# Decoup_Cap_1.net
KiCad netlist of a schematic drawn in Altium Designer
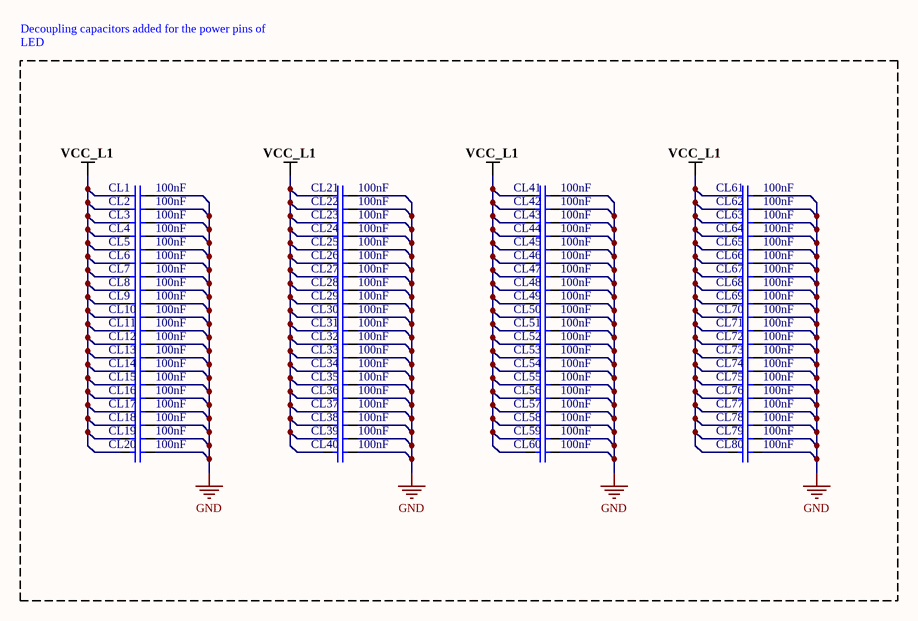
[diagram p0: Decoup_Cap 1.SchDoc]

(export (version "E")
  (design (tool "Eeschema 10.0.6"))
  (components
    (comp (ref "CL1")
      (value "100nF")
      (footprint "Cap0402")
      (description "Cap Ceramic 0.1uF 25V X7R 10% SMD 0402 125C Paper T/R")
      (fields
        (field (name "MANUFACTURER") "Yageo")
        (field (name "MANUFACTURER PART NUMBER") "CC0402KRX7R8BB104")
      )
      (libsource (lib "TT_IntLib") (part "CC0402KRX7R8BB104"))
    )
    (comp (ref "CL2")
      (value "100nF")
      (footprint "Cap0402")
      (description "Cap Ceramic 0.1uF 25V X7R 10% SMD 0402 125C Paper T/R")
      (fields
        (field (name "MANUFACTURER") "Yageo")
        (field (name "MANUFACTURER PART NUMBER") "CC0402KRX7R8BB104")
      )
      (libsource (lib "TT_IntLib") (part "CC0402KRX7R8BB104"))
    )
    (comp (ref "CL3")
      (value "100nF")
      (footprint "Cap0402")
      (description "Cap Ceramic 0.1uF 25V X7R 10% SMD 0402 125C Paper T/R")
      (fields
        (field (name "MANUFACTURER") "Yageo")
        (field (name "MANUFACTURER PART NUMBER") "CC0402KRX7R8BB104")
      )
      (libsource (lib "TT_IntLib") (part "CC0402KRX7R8BB104"))
    )
    (comp (ref "CL4")
      (value "100nF")
      (footprint "Cap0402")
      (description "Cap Ceramic 0.1uF 25V X7R 10% SMD 0402 125C Paper T/R")
      (fields
        (field (name "MANUFACTURER") "Yageo")
        (field (name "MANUFACTURER PART NUMBER") "CC0402KRX7R8BB104")
      )
      (libsource (lib "TT_IntLib") (part "CC0402KRX7R8BB104"))
    )
    (comp (ref "CL5")
      (value "100nF")
      (footprint "Cap0402")
      (description "Cap Ceramic 0.1uF 25V X7R 10% SMD 0402 125C Paper T/R")
      (fields
        (field (name "MANUFACTURER") "Yageo")
        (field (name "MANUFACTURER PART NUMBER") "CC0402KRX7R8BB104")
      )
      (libsource (lib "TT_IntLib") (part "CC0402KRX7R8BB104"))
    )
    (comp (ref "CL6")
      (value "100nF")
      (footprint "Cap0402")
      (description "Cap Ceramic 0.1uF 25V X7R 10% SMD 0402 125C Paper T/R")
      (fields
        (field (name "MANUFACTURER") "Yageo")
        (field (name "MANUFACTURER PART NUMBER") "CC0402KRX7R8BB104")
      )
      (libsource (lib "TT_IntLib") (part "CC0402KRX7R8BB104"))
    )
    (comp (ref "CL7")
      (value "100nF")
      (footprint "Cap0402")
      (description "Cap Ceramic 0.1uF 25V X7R 10% SMD 0402 125C Paper T/R")
      (fields
        (field (name "MANUFACTURER") "Yageo")
        (field (name "MANUFACTURER PART NUMBER") "CC0402KRX7R8BB104")
      )
      (libsource (lib "TT_IntLib") (part "CC0402KRX7R8BB104"))
    )
    (comp (ref "CL8")
      (value "100nF")
      (footprint "Cap0402")
      (description "Cap Ceramic 0.1uF 25V X7R 10% SMD 0402 125C Paper T/R")
      (fields
        (field (name "MANUFACTURER") "Yageo")
        (field (name "MANUFACTURER PART NUMBER") "CC0402KRX7R8BB104")
      )
      (libsource (lib "TT_IntLib") (part "CC0402KRX7R8BB104"))
    )
    (comp (ref "CL9")
      (value "100nF")
      (footprint "Cap0402")
      (description "Cap Ceramic 0.1uF 25V X7R 10% SMD 0402 125C Paper T/R")
      (fields
        (field (name "MANUFACTURER") "Yageo")
        (field (name "MANUFACTURER PART NUMBER") "CC0402KRX7R8BB104")
      )
      (libsource (lib "TT_IntLib") (part "CC0402KRX7R8BB104"))
    )
    (comp (ref "CL10")
      (value "100nF")
      (footprint "Cap0402")
      (description "Cap Ceramic 0.1uF 25V X7R 10% SMD 0402 125C Paper T/R")
      (fields
        (field (name "MANUFACTURER") "Yageo")
        (field (name "MANUFACTURER PART NUMBER") "CC0402KRX7R8BB104")
      )
      (libsource (lib "TT_IntLib") (part "CC0402KRX7R8BB104"))
    )
    (comp (ref "CL11")
      (value "100nF")
      (footprint "Cap0402")
      (description "Cap Ceramic 0.1uF 25V X7R 10% SMD 0402 125C Paper T/R")
      (fields
        (field (name "MANUFACTURER") "Yageo")
        (field (name "MANUFACTURER PART NUMBER") "CC0402KRX7R8BB104")
      )
      (libsource (lib "TT_IntLib") (part "CC0402KRX7R8BB104"))
    )
    (comp (ref "CL12")
      (value "100nF")
      (footprint "Cap0402")
      (description "Cap Ceramic 0.1uF 25V X7R 10% SMD 0402 125C Paper T/R")
      (fields
        (field (name "MANUFACTURER") "Yageo")
        (field (name "MANUFACTURER PART NUMBER") "CC0402KRX7R8BB104")
      )
      (libsource (lib "TT_IntLib") (part "CC0402KRX7R8BB104"))
    )
    (comp (ref "CL13")
      (value "100nF")
      (footprint "Cap0402")
      (description "Cap Ceramic 0.1uF 25V X7R 10% SMD 0402 125C Paper T/R")
      (fields
        (field (name "MANUFACTURER") "Yageo")
        (field (name "MANUFACTURER PART NUMBER") "CC0402KRX7R8BB104")
      )
      (libsource (lib "TT_IntLib") (part "CC0402KRX7R8BB104"))
    )
    (comp (ref "CL14")
      (value "100nF")
      (footprint "Cap0402")
      (description "Cap Ceramic 0.1uF 25V X7R 10% SMD 0402 125C Paper T/R")
      (fields
        (field (name "MANUFACTURER") "Yageo")
        (field (name "MANUFACTURER PART NUMBER") "CC0402KRX7R8BB104")
      )
      (libsource (lib "TT_IntLib") (part "CC0402KRX7R8BB104"))
    )
    (comp (ref "CL15")
      (value "100nF")
      (footprint "Cap0402")
      (description "Cap Ceramic 0.1uF 25V X7R 10% SMD 0402 125C Paper T/R")
      (fields
        (field (name "MANUFACTURER") "Yageo")
        (field (name "MANUFACTURER PART NUMBER") "CC0402KRX7R8BB104")
      )
      (libsource (lib "TT_IntLib") (part "CC0402KRX7R8BB104"))
    )
    (comp (ref "CL16")
      (value "100nF")
      (footprint "Cap0402")
      (description "Cap Ceramic 0.1uF 25V X7R 10% SMD 0402 125C Paper T/R")
      (fields
        (field (name "MANUFACTURER") "Yageo")
        (field (name "MANUFACTURER PART NUMBER") "CC0402KRX7R8BB104")
      )
      (libsource (lib "TT_IntLib") (part "CC0402KRX7R8BB104"))
    )
    (comp (ref "CL17")
      (value "100nF")
      (footprint "Cap0402")
      (description "Cap Ceramic 0.1uF 25V X7R 10% SMD 0402 125C Paper T/R")
      (fields
        (field (name "MANUFACTURER") "Yageo")
        (field (name "MANUFACTURER PART NUMBER") "CC0402KRX7R8BB104")
      )
      (libsource (lib "TT_IntLib") (part "CC0402KRX7R8BB104"))
    )
    (comp (ref "CL18")
      (value "100nF")
      (footprint "Cap0402")
      (description "Cap Ceramic 0.1uF 25V X7R 10% SMD 0402 125C Paper T/R")
      (fields
        (field (name "MANUFACTURER") "Yageo")
        (field (name "MANUFACTURER PART NUMBER") "CC0402KRX7R8BB104")
      )
      (libsource (lib "TT_IntLib") (part "CC0402KRX7R8BB104"))
    )
    (comp (ref "CL19")
      (value "100nF")
      (footprint "Cap0402")
      (description "Cap Ceramic 0.1uF 25V X7R 10% SMD 0402 125C Paper T/R")
      (fields
        (field (name "MANUFACTURER") "Yageo")
        (field (name "MANUFACTURER PART NUMBER") "CC0402KRX7R8BB104")
      )
      (libsource (lib "TT_IntLib") (part "CC0402KRX7R8BB104"))
    )
    (comp (ref "CL20")
      (value "100nF")
      (footprint "Cap0402")
      (description "Cap Ceramic 0.1uF 25V X7R 10% SMD 0402 125C Paper T/R")
      (fields
        (field (name "MANUFACTURER") "Yageo")
        (field (name "MANUFACTURER PART NUMBER") "CC0402KRX7R8BB104")
      )
      (libsource (lib "TT_IntLib") (part "CC0402KRX7R8BB104"))
    )
    (comp (ref "CL21")
      (value "100nF")
      (footprint "Cap0402")
      (description "Cap Ceramic 0.1uF 25V X7R 10% SMD 0402 125C Paper T/R")
      (fields
        (field (name "MANUFACTURER") "Yageo")
        (field (name "MANUFACTURER PART NUMBER") "CC0402KRX7R8BB104")
      )
      (libsource (lib "TT_IntLib") (part "CC0402KRX7R8BB104"))
    )
    (comp (ref "CL22")
      (value "100nF")
      (footprint "Cap0402")
      (description "Cap Ceramic 0.1uF 25V X7R 10% SMD 0402 125C Paper T/R")
      (fields
        (field (name "MANUFACTURER") "Yageo")
        (field (name "MANUFACTURER PART NUMBER") "CC0402KRX7R8BB104")
      )
      (libsource (lib "TT_IntLib") (part "CC0402KRX7R8BB104"))
    )
    (comp (ref "CL23")
      (value "100nF")
      (footprint "Cap0402")
      (description "Cap Ceramic 0.1uF 25V X7R 10% SMD 0402 125C Paper T/R")
      (fields
        (field (name "MANUFACTURER") "Yageo")
        (field (name "MANUFACTURER PART NUMBER") "CC0402KRX7R8BB104")
      )
      (libsource (lib "TT_IntLib") (part "CC0402KRX7R8BB104"))
    )
    (comp (ref "CL24")
      (value "100nF")
      (footprint "Cap0402")
      (description "Cap Ceramic 0.1uF 25V X7R 10% SMD 0402 125C Paper T/R")
      (fields
        (field (name "MANUFACTURER") "Yageo")
        (field (name "MANUFACTURER PART NUMBER") "CC0402KRX7R8BB104")
      )
      (libsource (lib "TT_IntLib") (part "CC0402KRX7R8BB104"))
    )
    (comp (ref "CL25")
      (value "100nF")
      (footprint "Cap0402")
      (description "Cap Ceramic 0.1uF 25V X7R 10% SMD 0402 125C Paper T/R")
      (fields
        (field (name "MANUFACTURER") "Yageo")
        (field (name "MANUFACTURER PART NUMBER") "CC0402KRX7R8BB104")
      )
      (libsource (lib "TT_IntLib") (part "CC0402KRX7R8BB104"))
    )
    (comp (ref "CL26")
      (value "100nF")
      (footprint "Cap0402")
      (description "Cap Ceramic 0.1uF 25V X7R 10% SMD 0402 125C Paper T/R")
      (fields
        (field (name "MANUFACTURER") "Yageo")
        (field (name "MANUFACTURER PART NUMBER") "CC0402KRX7R8BB104")
      )
      (libsource (lib "TT_IntLib") (part "CC0402KRX7R8BB104"))
    )
    (comp (ref "CL27")
      (value "100nF")
      (footprint "Cap0402")
      (description "Cap Ceramic 0.1uF 25V X7R 10% SMD 0402 125C Paper T/R")
      (fields
        (field (name "MANUFACTURER") "Yageo")
        (field (name "MANUFACTURER PART NUMBER") "CC0402KRX7R8BB104")
      )
      (libsource (lib "TT_IntLib") (part "CC0402KRX7R8BB104"))
    )
    (comp (ref "CL28")
      (value "100nF")
      (footprint "Cap0402")
      (description "Cap Ceramic 0.1uF 25V X7R 10% SMD 0402 125C Paper T/R")
      (fields
        (field (name "MANUFACTURER") "Yageo")
        (field (name "MANUFACTURER PART NUMBER") "CC0402KRX7R8BB104")
      )
      (libsource (lib "TT_IntLib") (part "CC0402KRX7R8BB104"))
    )
    (comp (ref "CL29")
      (value "100nF")
      (footprint "Cap0402")
      (description "Cap Ceramic 0.1uF 25V X7R 10% SMD 0402 125C Paper T/R")
      (fields
        (field (name "MANUFACTURER") "Yageo")
        (field (name "MANUFACTURER PART NUMBER") "CC0402KRX7R8BB104")
      )
      (libsource (lib "TT_IntLib") (part "CC0402KRX7R8BB104"))
    )
    (comp (ref "CL30")
      (value "100nF")
      (footprint "Cap0402")
      (description "Cap Ceramic 0.1uF 25V X7R 10% SMD 0402 125C Paper T/R")
      (fields
        (field (name "MANUFACTURER") "Yageo")
        (field (name "MANUFACTURER PART NUMBER") "CC0402KRX7R8BB104")
      )
      (libsource (lib "TT_IntLib") (part "CC0402KRX7R8BB104"))
    )
    (comp (ref "CL31")
      (value "100nF")
      (footprint "Cap0402")
      (description "Cap Ceramic 0.1uF 25V X7R 10% SMD 0402 125C Paper T/R")
      (fields
        (field (name "MANUFACTURER") "Yageo")
        (field (name "MANUFACTURER PART NUMBER") "CC0402KRX7R8BB104")
      )
      (libsource (lib "TT_IntLib") (part "CC0402KRX7R8BB104"))
    )
    (comp (ref "CL32")
      (value "100nF")
      (footprint "Cap0402")
      (description "Cap Ceramic 0.1uF 25V X7R 10% SMD 0402 125C Paper T/R")
      (fields
        (field (name "MANUFACTURER") "Yageo")
        (field (name "MANUFACTURER PART NUMBER") "CC0402KRX7R8BB104")
      )
      (libsource (lib "TT_IntLib") (part "CC0402KRX7R8BB104"))
    )
    (comp (ref "CL33")
      (value "100nF")
      (footprint "Cap0402")
      (description "Cap Ceramic 0.1uF 25V X7R 10% SMD 0402 125C Paper T/R")
      (fields
        (field (name "MANUFACTURER") "Yageo")
        (field (name "MANUFACTURER PART NUMBER") "CC0402KRX7R8BB104")
      )
      (libsource (lib "TT_IntLib") (part "CC0402KRX7R8BB104"))
    )
    (comp (ref "CL34")
      (value "100nF")
      (footprint "Cap0402")
      (description "Cap Ceramic 0.1uF 25V X7R 10% SMD 0402 125C Paper T/R")
      (fields
        (field (name "MANUFACTURER") "Yageo")
        (field (name "MANUFACTURER PART NUMBER") "CC0402KRX7R8BB104")
      )
      (libsource (lib "TT_IntLib") (part "CC0402KRX7R8BB104"))
    )
    (comp (ref "CL35")
      (value "100nF")
      (footprint "Cap0402")
      (description "Cap Ceramic 0.1uF 25V X7R 10% SMD 0402 125C Paper T/R")
      (fields
        (field (name "MANUFACTURER") "Yageo")
        (field (name "MANUFACTURER PART NUMBER") "CC0402KRX7R8BB104")
      )
      (libsource (lib "TT_IntLib") (part "CC0402KRX7R8BB104"))
    )
    (comp (ref "CL36")
      (value "100nF")
      (footprint "Cap0402")
      (description "Cap Ceramic 0.1uF 25V X7R 10% SMD 0402 125C Paper T/R")
      (fields
        (field (name "MANUFACTURER") "Yageo")
        (field (name "MANUFACTURER PART NUMBER") "CC0402KRX7R8BB104")
      )
      (libsource (lib "TT_IntLib") (part "CC0402KRX7R8BB104"))
    )
    (comp (ref "CL37")
      (value "100nF")
      (footprint "Cap0402")
      (description "Cap Ceramic 0.1uF 25V X7R 10% SMD 0402 125C Paper T/R")
      (fields
        (field (name "MANUFACTURER") "Yageo")
        (field (name "MANUFACTURER PART NUMBER") "CC0402KRX7R8BB104")
      )
      (libsource (lib "TT_IntLib") (part "CC0402KRX7R8BB104"))
    )
    (comp (ref "CL38")
      (value "100nF")
      (footprint "Cap0402")
      (description "Cap Ceramic 0.1uF 25V X7R 10% SMD 0402 125C Paper T/R")
      (fields
        (field (name "MANUFACTURER") "Yageo")
        (field (name "MANUFACTURER PART NUMBER") "CC0402KRX7R8BB104")
      )
      (libsource (lib "TT_IntLib") (part "CC0402KRX7R8BB104"))
    )
    (comp (ref "CL39")
      (value "100nF")
      (footprint "Cap0402")
      (description "Cap Ceramic 0.1uF 25V X7R 10% SMD 0402 125C Paper T/R")
      (fields
        (field (name "MANUFACTURER") "Yageo")
        (field (name "MANUFACTURER PART NUMBER") "CC0402KRX7R8BB104")
      )
      (libsource (lib "TT_IntLib") (part "CC0402KRX7R8BB104"))
    )
    (comp (ref "CL40")
      (value "100nF")
      (footprint "Cap0402")
      (description "Cap Ceramic 0.1uF 25V X7R 10% SMD 0402 125C Paper T/R")
      (fields
        (field (name "MANUFACTURER") "Yageo")
        (field (name "MANUFACTURER PART NUMBER") "CC0402KRX7R8BB104")
      )
      (libsource (lib "TT_IntLib") (part "CC0402KRX7R8BB104"))
    )
    (comp (ref "CL41")
      (value "100nF")
      (footprint "Cap0402")
      (description "Cap Ceramic 0.1uF 25V X7R 10% SMD 0402 125C Paper T/R")
      (fields
        (field (name "MANUFACTURER") "Yageo")
        (field (name "MANUFACTURER PART NUMBER") "CC0402KRX7R8BB104")
      )
      (libsource (lib "TT_IntLib") (part "CC0402KRX7R8BB104"))
    )
    (comp (ref "CL42")
      (value "100nF")
      (footprint "Cap0402")
      (description "Cap Ceramic 0.1uF 25V X7R 10% SMD 0402 125C Paper T/R")
      (fields
        (field (name "MANUFACTURER") "Yageo")
        (field (name "MANUFACTURER PART NUMBER") "CC0402KRX7R8BB104")
      )
      (libsource (lib "TT_IntLib") (part "CC0402KRX7R8BB104"))
    )
    (comp (ref "CL43")
      (value "100nF")
      (footprint "Cap0402")
      (description "Cap Ceramic 0.1uF 25V X7R 10% SMD 0402 125C Paper T/R")
      (fields
        (field (name "MANUFACTURER") "Yageo")
        (field (name "MANUFACTURER PART NUMBER") "CC0402KRX7R8BB104")
      )
      (libsource (lib "TT_IntLib") (part "CC0402KRX7R8BB104"))
    )
    (comp (ref "CL44")
      (value "100nF")
      (footprint "Cap0402")
      (description "Cap Ceramic 0.1uF 25V X7R 10% SMD 0402 125C Paper T/R")
      (fields
        (field (name "MANUFACTURER") "Yageo")
        (field (name "MANUFACTURER PART NUMBER") "CC0402KRX7R8BB104")
      )
      (libsource (lib "TT_IntLib") (part "CC0402KRX7R8BB104"))
    )
    (comp (ref "CL45")
      (value "100nF")
      (footprint "Cap0402")
      (description "Cap Ceramic 0.1uF 25V X7R 10% SMD 0402 125C Paper T/R")
      (fields
        (field (name "MANUFACTURER") "Yageo")
        (field (name "MANUFACTURER PART NUMBER") "CC0402KRX7R8BB104")
      )
      (libsource (lib "TT_IntLib") (part "CC0402KRX7R8BB104"))
    )
    (comp (ref "CL46")
      (value "100nF")
      (footprint "Cap0402")
      (description "Cap Ceramic 0.1uF 25V X7R 10% SMD 0402 125C Paper T/R")
      (fields
        (field (name "MANUFACTURER") "Yageo")
        (field (name "MANUFACTURER PART NUMBER") "CC0402KRX7R8BB104")
      )
      (libsource (lib "TT_IntLib") (part "CC0402KRX7R8BB104"))
    )
    (comp (ref "CL47")
      (value "100nF")
      (footprint "Cap0402")
      (description "Cap Ceramic 0.1uF 25V X7R 10% SMD 0402 125C Paper T/R")
      (fields
        (field (name "MANUFACTURER") "Yageo")
        (field (name "MANUFACTURER PART NUMBER") "CC0402KRX7R8BB104")
      )
      (libsource (lib "TT_IntLib") (part "CC0402KRX7R8BB104"))
    )
    (comp (ref "CL48")
      (value "100nF")
      (footprint "Cap0402")
      (description "Cap Ceramic 0.1uF 25V X7R 10% SMD 0402 125C Paper T/R")
      (fields
        (field (name "MANUFACTURER") "Yageo")
        (field (name "MANUFACTURER PART NUMBER") "CC0402KRX7R8BB104")
      )
      (libsource (lib "TT_IntLib") (part "CC0402KRX7R8BB104"))
    )
    (comp (ref "CL49")
      (value "100nF")
      (footprint "Cap0402")
      (description "Cap Ceramic 0.1uF 25V X7R 10% SMD 0402 125C Paper T/R")
      (fields
        (field (name "MANUFACTURER") "Yageo")
        (field (name "MANUFACTURER PART NUMBER") "CC0402KRX7R8BB104")
      )
      (libsource (lib "TT_IntLib") (part "CC0402KRX7R8BB104"))
    )
    (comp (ref "CL50")
      (value "100nF")
      (footprint "Cap0402")
      (description "Cap Ceramic 0.1uF 25V X7R 10% SMD 0402 125C Paper T/R")
      (fields
        (field (name "MANUFACTURER") "Yageo")
        (field (name "MANUFACTURER PART NUMBER") "CC0402KRX7R8BB104")
      )
      (libsource (lib "TT_IntLib") (part "CC0402KRX7R8BB104"))
    )
    (comp (ref "CL51")
      (value "100nF")
      (footprint "Cap0402")
      (description "Cap Ceramic 0.1uF 25V X7R 10% SMD 0402 125C Paper T/R")
      (fields
        (field (name "MANUFACTURER") "Yageo")
        (field (name "MANUFACTURER PART NUMBER") "CC0402KRX7R8BB104")
      )
      (libsource (lib "TT_IntLib") (part "CC0402KRX7R8BB104"))
    )
    (comp (ref "CL52")
      (value "100nF")
      (footprint "Cap0402")
      (description "Cap Ceramic 0.1uF 25V X7R 10% SMD 0402 125C Paper T/R")
      (fields
        (field (name "MANUFACTURER") "Yageo")
        (field (name "MANUFACTURER PART NUMBER") "CC0402KRX7R8BB104")
      )
      (libsource (lib "TT_IntLib") (part "CC0402KRX7R8BB104"))
    )
    (comp (ref "CL53")
      (value "100nF")
      (footprint "Cap0402")
      (description "Cap Ceramic 0.1uF 25V X7R 10% SMD 0402 125C Paper T/R")
      (fields
        (field (name "MANUFACTURER") "Yageo")
        (field (name "MANUFACTURER PART NUMBER") "CC0402KRX7R8BB104")
      )
      (libsource (lib "TT_IntLib") (part "CC0402KRX7R8BB104"))
    )
    (comp (ref "CL54")
      (value "100nF")
      (footprint "Cap0402")
      (description "Cap Ceramic 0.1uF 25V X7R 10% SMD 0402 125C Paper T/R")
      (fields
        (field (name "MANUFACTURER") "Yageo")
        (field (name "MANUFACTURER PART NUMBER") "CC0402KRX7R8BB104")
      )
      (libsource (lib "TT_IntLib") (part "CC0402KRX7R8BB104"))
    )
    (comp (ref "CL55")
      (value "100nF")
      (footprint "Cap0402")
      (description "Cap Ceramic 0.1uF 25V X7R 10% SMD 0402 125C Paper T/R")
      (fields
        (field (name "MANUFACTURER") "Yageo")
        (field (name "MANUFACTURER PART NUMBER") "CC0402KRX7R8BB104")
      )
      (libsource (lib "TT_IntLib") (part "CC0402KRX7R8BB104"))
    )
    (comp (ref "CL56")
      (value "100nF")
      (footprint "Cap0402")
      (description "Cap Ceramic 0.1uF 25V X7R 10% SMD 0402 125C Paper T/R")
      (fields
        (field (name "MANUFACTURER") "Yageo")
        (field (name "MANUFACTURER PART NUMBER") "CC0402KRX7R8BB104")
      )
      (libsource (lib "TT_IntLib") (part "CC0402KRX7R8BB104"))
    )
    (comp (ref "CL57")
      (value "100nF")
      (footprint "Cap0402")
      (description "Cap Ceramic 0.1uF 25V X7R 10% SMD 0402 125C Paper T/R")
      (fields
        (field (name "MANUFACTURER") "Yageo")
        (field (name "MANUFACTURER PART NUMBER") "CC0402KRX7R8BB104")
      )
      (libsource (lib "TT_IntLib") (part "CC0402KRX7R8BB104"))
    )
    (comp (ref "CL58")
      (value "100nF")
      (footprint "Cap0402")
      (description "Cap Ceramic 0.1uF 25V X7R 10% SMD 0402 125C Paper T/R")
      (fields
        (field (name "MANUFACTURER") "Yageo")
        (field (name "MANUFACTURER PART NUMBER") "CC0402KRX7R8BB104")
      )
      (libsource (lib "TT_IntLib") (part "CC0402KRX7R8BB104"))
    )
    (comp (ref "CL59")
      (value "100nF")
      (footprint "Cap0402")
      (description "Cap Ceramic 0.1uF 25V X7R 10% SMD 0402 125C Paper T/R")
      (fields
        (field (name "MANUFACTURER") "Yageo")
        (field (name "MANUFACTURER PART NUMBER") "CC0402KRX7R8BB104")
      )
      (libsource (lib "TT_IntLib") (part "CC0402KRX7R8BB104"))
    )
    (comp (ref "CL60")
      (value "100nF")
      (footprint "Cap0402")
      (description "Cap Ceramic 0.1uF 25V X7R 10% SMD 0402 125C Paper T/R")
      (fields
        (field (name "MANUFACTURER") "Yageo")
        (field (name "MANUFACTURER PART NUMBER") "CC0402KRX7R8BB104")
      )
      (libsource (lib "TT_IntLib") (part "CC0402KRX7R8BB104"))
    )
    (comp (ref "CL61")
      (value "100nF")
      (footprint "Cap0402")
      (description "Cap Ceramic 0.1uF 25V X7R 10% SMD 0402 125C Paper T/R")
      (fields
        (field (name "MANUFACTURER") "Yageo")
        (field (name "MANUFACTURER PART NUMBER") "CC0402KRX7R8BB104")
      )
      (libsource (lib "TT_IntLib") (part "CC0402KRX7R8BB104"))
    )
    (comp (ref "CL62")
      (value "100nF")
      (footprint "Cap0402")
      (description "Cap Ceramic 0.1uF 25V X7R 10% SMD 0402 125C Paper T/R")
      (fields
        (field (name "MANUFACTURER") "Yageo")
        (field (name "MANUFACTURER PART NUMBER") "CC0402KRX7R8BB104")
      )
      (libsource (lib "TT_IntLib") (part "CC0402KRX7R8BB104"))
    )
    (comp (ref "CL63")
      (value "100nF")
      (footprint "Cap0402")
      (description "Cap Ceramic 0.1uF 25V X7R 10% SMD 0402 125C Paper T/R")
      (fields
        (field (name "MANUFACTURER") "Yageo")
        (field (name "MANUFACTURER PART NUMBER") "CC0402KRX7R8BB104")
      )
      (libsource (lib "TT_IntLib") (part "CC0402KRX7R8BB104"))
    )
    (comp (ref "CL64")
      (value "100nF")
      (footprint "Cap0402")
      (description "Cap Ceramic 0.1uF 25V X7R 10% SMD 0402 125C Paper T/R")
      (fields
        (field (name "MANUFACTURER") "Yageo")
        (field (name "MANUFACTURER PART NUMBER") "CC0402KRX7R8BB104")
      )
      (libsource (lib "TT_IntLib") (part "CC0402KRX7R8BB104"))
    )
    (comp (ref "CL65")
      (value "100nF")
      (footprint "Cap0402")
      (description "Cap Ceramic 0.1uF 25V X7R 10% SMD 0402 125C Paper T/R")
      (fields
        (field (name "MANUFACTURER") "Yageo")
        (field (name "MANUFACTURER PART NUMBER") "CC0402KRX7R8BB104")
      )
      (libsource (lib "TT_IntLib") (part "CC0402KRX7R8BB104"))
    )
    (comp (ref "CL66")
      (value "100nF")
      (footprint "Cap0402")
      (description "Cap Ceramic 0.1uF 25V X7R 10% SMD 0402 125C Paper T/R")
      (fields
        (field (name "MANUFACTURER") "Yageo")
        (field (name "MANUFACTURER PART NUMBER") "CC0402KRX7R8BB104")
      )
      (libsource (lib "TT_IntLib") (part "CC0402KRX7R8BB104"))
    )
    (comp (ref "CL67")
      (value "100nF")
      (footprint "Cap0402")
      (description "Cap Ceramic 0.1uF 25V X7R 10% SMD 0402 125C Paper T/R")
      (fields
        (field (name "MANUFACTURER") "Yageo")
        (field (name "MANUFACTURER PART NUMBER") "CC0402KRX7R8BB104")
      )
      (libsource (lib "TT_IntLib") (part "CC0402KRX7R8BB104"))
    )
    (comp (ref "CL68")
      (value "100nF")
      (footprint "Cap0402")
      (description "Cap Ceramic 0.1uF 25V X7R 10% SMD 0402 125C Paper T/R")
      (fields
        (field (name "MANUFACTURER") "Yageo")
        (field (name "MANUFACTURER PART NUMBER") "CC0402KRX7R8BB104")
      )
      (libsource (lib "TT_IntLib") (part "CC0402KRX7R8BB104"))
    )
    (comp (ref "CL69")
      (value "100nF")
      (footprint "Cap0402")
      (description "Cap Ceramic 0.1uF 25V X7R 10% SMD 0402 125C Paper T/R")
      (fields
        (field (name "MANUFACTURER") "Yageo")
        (field (name "MANUFACTURER PART NUMBER") "CC0402KRX7R8BB104")
      )
      (libsource (lib "TT_IntLib") (part "CC0402KRX7R8BB104"))
    )
    (comp (ref "CL70")
      (value "100nF")
      (footprint "Cap0402")
      (description "Cap Ceramic 0.1uF 25V X7R 10% SMD 0402 125C Paper T/R")
      (fields
        (field (name "MANUFACTURER") "Yageo")
        (field (name "MANUFACTURER PART NUMBER") "CC0402KRX7R8BB104")
      )
      (libsource (lib "TT_IntLib") (part "CC0402KRX7R8BB104"))
    )
    (comp (ref "CL71")
      (value "100nF")
      (footprint "Cap0402")
      (description "Cap Ceramic 0.1uF 25V X7R 10% SMD 0402 125C Paper T/R")
      (fields
        (field (name "MANUFACTURER") "Yageo")
        (field (name "MANUFACTURER PART NUMBER") "CC0402KRX7R8BB104")
      )
      (libsource (lib "TT_IntLib") (part "CC0402KRX7R8BB104"))
    )
    (comp (ref "CL72")
      (value "100nF")
      (footprint "Cap0402")
      (description "Cap Ceramic 0.1uF 25V X7R 10% SMD 0402 125C Paper T/R")
      (fields
        (field (name "MANUFACTURER") "Yageo")
        (field (name "MANUFACTURER PART NUMBER") "CC0402KRX7R8BB104")
      )
      (libsource (lib "TT_IntLib") (part "CC0402KRX7R8BB104"))
    )
    (comp (ref "CL73")
      (value "100nF")
      (footprint "Cap0402")
      (description "Cap Ceramic 0.1uF 25V X7R 10% SMD 0402 125C Paper T/R")
      (fields
        (field (name "MANUFACTURER") "Yageo")
        (field (name "MANUFACTURER PART NUMBER") "CC0402KRX7R8BB104")
      )
      (libsource (lib "TT_IntLib") (part "CC0402KRX7R8BB104"))
    )
    (comp (ref "CL74")
      (value "100nF")
      (footprint "Cap0402")
      (description "Cap Ceramic 0.1uF 25V X7R 10% SMD 0402 125C Paper T/R")
      (fields
        (field (name "MANUFACTURER") "Yageo")
        (field (name "MANUFACTURER PART NUMBER") "CC0402KRX7R8BB104")
      )
      (libsource (lib "TT_IntLib") (part "CC0402KRX7R8BB104"))
    )
    (comp (ref "CL75")
      (value "100nF")
      (footprint "Cap0402")
      (description "Cap Ceramic 0.1uF 25V X7R 10% SMD 0402 125C Paper T/R")
      (fields
        (field (name "MANUFACTURER") "Yageo")
        (field (name "MANUFACTURER PART NUMBER") "CC0402KRX7R8BB104")
      )
      (libsource (lib "TT_IntLib") (part "CC0402KRX7R8BB104"))
    )
    (comp (ref "CL76")
      (value "100nF")
      (footprint "Cap0402")
      (description "Cap Ceramic 0.1uF 25V X7R 10% SMD 0402 125C Paper T/R")
      (fields
        (field (name "MANUFACTURER") "Yageo")
        (field (name "MANUFACTURER PART NUMBER") "CC0402KRX7R8BB104")
      )
      (libsource (lib "TT_IntLib") (part "CC0402KRX7R8BB104"))
    )
    (comp (ref "CL77")
      (value "100nF")
      (footprint "Cap0402")
      (description "Cap Ceramic 0.1uF 25V X7R 10% SMD 0402 125C Paper T/R")
      (fields
        (field (name "MANUFACTURER") "Yageo")
        (field (name "MANUFACTURER PART NUMBER") "CC0402KRX7R8BB104")
      )
      (libsource (lib "TT_IntLib") (part "CC0402KRX7R8BB104"))
    )
    (comp (ref "CL78")
      (value "100nF")
      (footprint "Cap0402")
      (description "Cap Ceramic 0.1uF 25V X7R 10% SMD 0402 125C Paper T/R")
      (fields
        (field (name "MANUFACTURER") "Yageo")
        (field (name "MANUFACTURER PART NUMBER") "CC0402KRX7R8BB104")
      )
      (libsource (lib "TT_IntLib") (part "CC0402KRX7R8BB104"))
    )
    (comp (ref "CL79")
      (value "100nF")
      (footprint "Cap0402")
      (description "Cap Ceramic 0.1uF 25V X7R 10% SMD 0402 125C Paper T/R")
      (fields
        (field (name "MANUFACTURER") "Yageo")
        (field (name "MANUFACTURER PART NUMBER") "CC0402KRX7R8BB104")
      )
      (libsource (lib "TT_IntLib") (part "CC0402KRX7R8BB104"))
    )
    (comp (ref "CL80")
      (value "100nF")
      (footprint "Cap0402")
      (description "Cap Ceramic 0.1uF 25V X7R 10% SMD 0402 125C Paper T/R")
      (fields
        (field (name "MANUFACTURER") "Yageo")
        (field (name "MANUFACTURER PART NUMBER") "CC0402KRX7R8BB104")
      )
      (libsource (lib "TT_IntLib") (part "CC0402KRX7R8BB104"))
    )
  )
  (nets
    (net (code "1") (name "GND") (class "Default")
      (node (ref "CL1") (pin "1") (pintype "passive"))
      (node (ref "CL10") (pin "1") (pintype "passive"))
      (node (ref "CL11") (pin "1") (pintype "passive"))
      (node (ref "CL12") (pin "1") (pintype "passive"))
      (node (ref "CL13") (pin "1") (pintype "passive"))
      (node (ref "CL14") (pin "1") (pintype "passive"))
      (node (ref "CL15") (pin "1") (pintype "passive"))
      (node (ref "CL16") (pin "1") (pintype "passive"))
      (node (ref "CL17") (pin "1") (pintype "passive"))
      (node (ref "CL18") (pin "1") (pintype "passive"))
      (node (ref "CL19") (pin "1") (pintype "passive"))
      (node (ref "CL2") (pin "1") (pintype "passive"))
      (node (ref "CL20") (pin "1") (pintype "passive"))
      (node (ref "CL21") (pin "1") (pintype "passive"))
      (node (ref "CL22") (pin "1") (pintype "passive"))
      (node (ref "CL23") (pin "1") (pintype "passive"))
      (node (ref "CL24") (pin "1") (pintype "passive"))
      (node (ref "CL25") (pin "1") (pintype "passive"))
      (node (ref "CL26") (pin "1") (pintype "passive"))
      (node (ref "CL27") (pin "1") (pintype "passive"))
      (node (ref "CL28") (pin "1") (pintype "passive"))
      (node (ref "CL29") (pin "1") (pintype "passive"))
      (node (ref "CL3") (pin "1") (pintype "passive"))
      (node (ref "CL30") (pin "1") (pintype "passive"))
      (node (ref "CL31") (pin "1") (pintype "passive"))
      (node (ref "CL32") (pin "1") (pintype "passive"))
      (node (ref "CL33") (pin "1") (pintype "passive"))
      (node (ref "CL34") (pin "1") (pintype "passive"))
      (node (ref "CL35") (pin "1") (pintype "passive"))
      (node (ref "CL36") (pin "1") (pintype "passive"))
      (node (ref "CL37") (pin "1") (pintype "passive"))
      (node (ref "CL38") (pin "1") (pintype "passive"))
      (node (ref "CL39") (pin "1") (pintype "passive"))
      (node (ref "CL4") (pin "1") (pintype "passive"))
      (node (ref "CL40") (pin "1") (pintype "passive"))
      (node (ref "CL41") (pin "1") (pintype "passive"))
      (node (ref "CL42") (pin "1") (pintype "passive"))
      (node (ref "CL43") (pin "1") (pintype "passive"))
      (node (ref "CL44") (pin "1") (pintype "passive"))
      (node (ref "CL45") (pin "1") (pintype "passive"))
      (node (ref "CL46") (pin "1") (pintype "passive"))
      (node (ref "CL47") (pin "1") (pintype "passive"))
      (node (ref "CL48") (pin "1") (pintype "passive"))
      (node (ref "CL49") (pin "1") (pintype "passive"))
      (node (ref "CL5") (pin "1") (pintype "passive"))
      (node (ref "CL50") (pin "1") (pintype "passive"))
      (node (ref "CL51") (pin "1") (pintype "passive"))
      (node (ref "CL52") (pin "1") (pintype "passive"))
      (node (ref "CL53") (pin "1") (pintype "passive"))
      (node (ref "CL54") (pin "1") (pintype "passive"))
      (node (ref "CL55") (pin "1") (pintype "passive"))
      (node (ref "CL56") (pin "1") (pintype "passive"))
      (node (ref "CL57") (pin "1") (pintype "passive"))
      (node (ref "CL58") (pin "1") (pintype "passive"))
      (node (ref "CL59") (pin "1") (pintype "passive"))
      (node (ref "CL6") (pin "1") (pintype "passive"))
      (node (ref "CL60") (pin "1") (pintype "passive"))
      (node (ref "CL61") (pin "1") (pintype "passive"))
      (node (ref "CL62") (pin "1") (pintype "passive"))
      (node (ref "CL63") (pin "1") (pintype "passive"))
      (node (ref "CL64") (pin "1") (pintype "passive"))
      (node (ref "CL65") (pin "1") (pintype "passive"))
      (node (ref "CL66") (pin "1") (pintype "passive"))
      (node (ref "CL67") (pin "1") (pintype "passive"))
      (node (ref "CL68") (pin "1") (pintype "passive"))
      (node (ref "CL69") (pin "1") (pintype "passive"))
      (node (ref "CL7") (pin "1") (pintype "passive"))
      (node (ref "CL70") (pin "1") (pintype "passive"))
      (node (ref "CL71") (pin "1") (pintype "passive"))
      (node (ref "CL72") (pin "1") (pintype "passive"))
      (node (ref "CL73") (pin "1") (pintype "passive"))
      (node (ref "CL74") (pin "1") (pintype "passive"))
      (node (ref "CL75") (pin "1") (pintype "passive"))
      (node (ref "CL76") (pin "1") (pintype "passive"))
      (node (ref "CL77") (pin "1") (pintype "passive"))
      (node (ref "CL78") (pin "1") (pintype "passive"))
      (node (ref "CL79") (pin "1") (pintype "passive"))
      (node (ref "CL8") (pin "1") (pintype "passive"))
      (node (ref "CL80") (pin "1") (pintype "passive"))
      (node (ref "CL9") (pin "1") (pintype "passive"))
    )
    (net (code "2") (name "VCC_L1") (class "Default")
      (node (ref "CL1") (pin "2") (pintype "passive"))
      (node (ref "CL10") (pin "2") (pintype "passive"))
      (node (ref "CL11") (pin "2") (pintype "passive"))
      (node (ref "CL12") (pin "2") (pintype "passive"))
      (node (ref "CL13") (pin "2") (pintype "passive"))
      (node (ref "CL14") (pin "2") (pintype "passive"))
      (node (ref "CL15") (pin "2") (pintype "passive"))
      (node (ref "CL16") (pin "2") (pintype "passive"))
      (node (ref "CL17") (pin "2") (pintype "passive"))
      (node (ref "CL18") (pin "2") (pintype "passive"))
      (node (ref "CL19") (pin "2") (pintype "passive"))
      (node (ref "CL2") (pin "2") (pintype "passive"))
      (node (ref "CL20") (pin "2") (pintype "passive"))
      (node (ref "CL21") (pin "2") (pintype "passive"))
      (node (ref "CL22") (pin "2") (pintype "passive"))
      (node (ref "CL23") (pin "2") (pintype "passive"))
      (node (ref "CL24") (pin "2") (pintype "passive"))
      (node (ref "CL25") (pin "2") (pintype "passive"))
      (node (ref "CL26") (pin "2") (pintype "passive"))
      (node (ref "CL27") (pin "2") (pintype "passive"))
      (node (ref "CL28") (pin "2") (pintype "passive"))
      (node (ref "CL29") (pin "2") (pintype "passive"))
      (node (ref "CL3") (pin "2") (pintype "passive"))
      (node (ref "CL30") (pin "2") (pintype "passive"))
      (node (ref "CL31") (pin "2") (pintype "passive"))
      (node (ref "CL32") (pin "2") (pintype "passive"))
      (node (ref "CL33") (pin "2") (pintype "passive"))
      (node (ref "CL34") (pin "2") (pintype "passive"))
      (node (ref "CL35") (pin "2") (pintype "passive"))
      (node (ref "CL36") (pin "2") (pintype "passive"))
      (node (ref "CL37") (pin "2") (pintype "passive"))
      (node (ref "CL38") (pin "2") (pintype "passive"))
      (node (ref "CL39") (pin "2") (pintype "passive"))
      (node (ref "CL4") (pin "2") (pintype "passive"))
      (node (ref "CL40") (pin "2") (pintype "passive"))
      (node (ref "CL41") (pin "2") (pintype "passive"))
      (node (ref "CL42") (pin "2") (pintype "passive"))
      (node (ref "CL43") (pin "2") (pintype "passive"))
      (node (ref "CL44") (pin "2") (pintype "passive"))
      (node (ref "CL45") (pin "2") (pintype "passive"))
      (node (ref "CL46") (pin "2") (pintype "passive"))
      (node (ref "CL47") (pin "2") (pintype "passive"))
      (node (ref "CL48") (pin "2") (pintype "passive"))
      (node (ref "CL49") (pin "2") (pintype "passive"))
      (node (ref "CL5") (pin "2") (pintype "passive"))
      (node (ref "CL50") (pin "2") (pintype "passive"))
      (node (ref "CL51") (pin "2") (pintype "passive"))
      (node (ref "CL52") (pin "2") (pintype "passive"))
      (node (ref "CL53") (pin "2") (pintype "passive"))
      (node (ref "CL54") (pin "2") (pintype "passive"))
      (node (ref "CL55") (pin "2") (pintype "passive"))
      (node (ref "CL56") (pin "2") (pintype "passive"))
      (node (ref "CL57") (pin "2") (pintype "passive"))
      (node (ref "CL58") (pin "2") (pintype "passive"))
      (node (ref "CL59") (pin "2") (pintype "passive"))
      (node (ref "CL6") (pin "2") (pintype "passive"))
      (node (ref "CL60") (pin "2") (pintype "passive"))
      (node (ref "CL61") (pin "2") (pintype "passive"))
      (node (ref "CL62") (pin "2") (pintype "passive"))
      (node (ref "CL63") (pin "2") (pintype "passive"))
      (node (ref "CL64") (pin "2") (pintype "passive"))
      (node (ref "CL65") (pin "2") (pintype "passive"))
      (node (ref "CL66") (pin "2") (pintype "passive"))
      (node (ref "CL67") (pin "2") (pintype "passive"))
      (node (ref "CL68") (pin "2") (pintype "passive"))
      (node (ref "CL69") (pin "2") (pintype "passive"))
      (node (ref "CL7") (pin "2") (pintype "passive"))
      (node (ref "CL70") (pin "2") (pintype "passive"))
      (node (ref "CL71") (pin "2") (pintype "passive"))
      (node (ref "CL72") (pin "2") (pintype "passive"))
      (node (ref "CL73") (pin "2") (pintype "passive"))
      (node (ref "CL74") (pin "2") (pintype "passive"))
      (node (ref "CL75") (pin "2") (pintype "passive"))
      (node (ref "CL76") (pin "2") (pintype "passive"))
      (node (ref "CL77") (pin "2") (pintype "passive"))
      (node (ref "CL78") (pin "2") (pintype "passive"))
      (node (ref "CL79") (pin "2") (pintype "passive"))
      (node (ref "CL8") (pin "2") (pintype "passive"))
      (node (ref "CL80") (pin "2") (pintype "passive"))
      (node (ref "CL9") (pin "2") (pintype "passive"))
    )
  )
)
